# Peripherals.net
KiCad netlist of a schematic drawn in Altium Designer
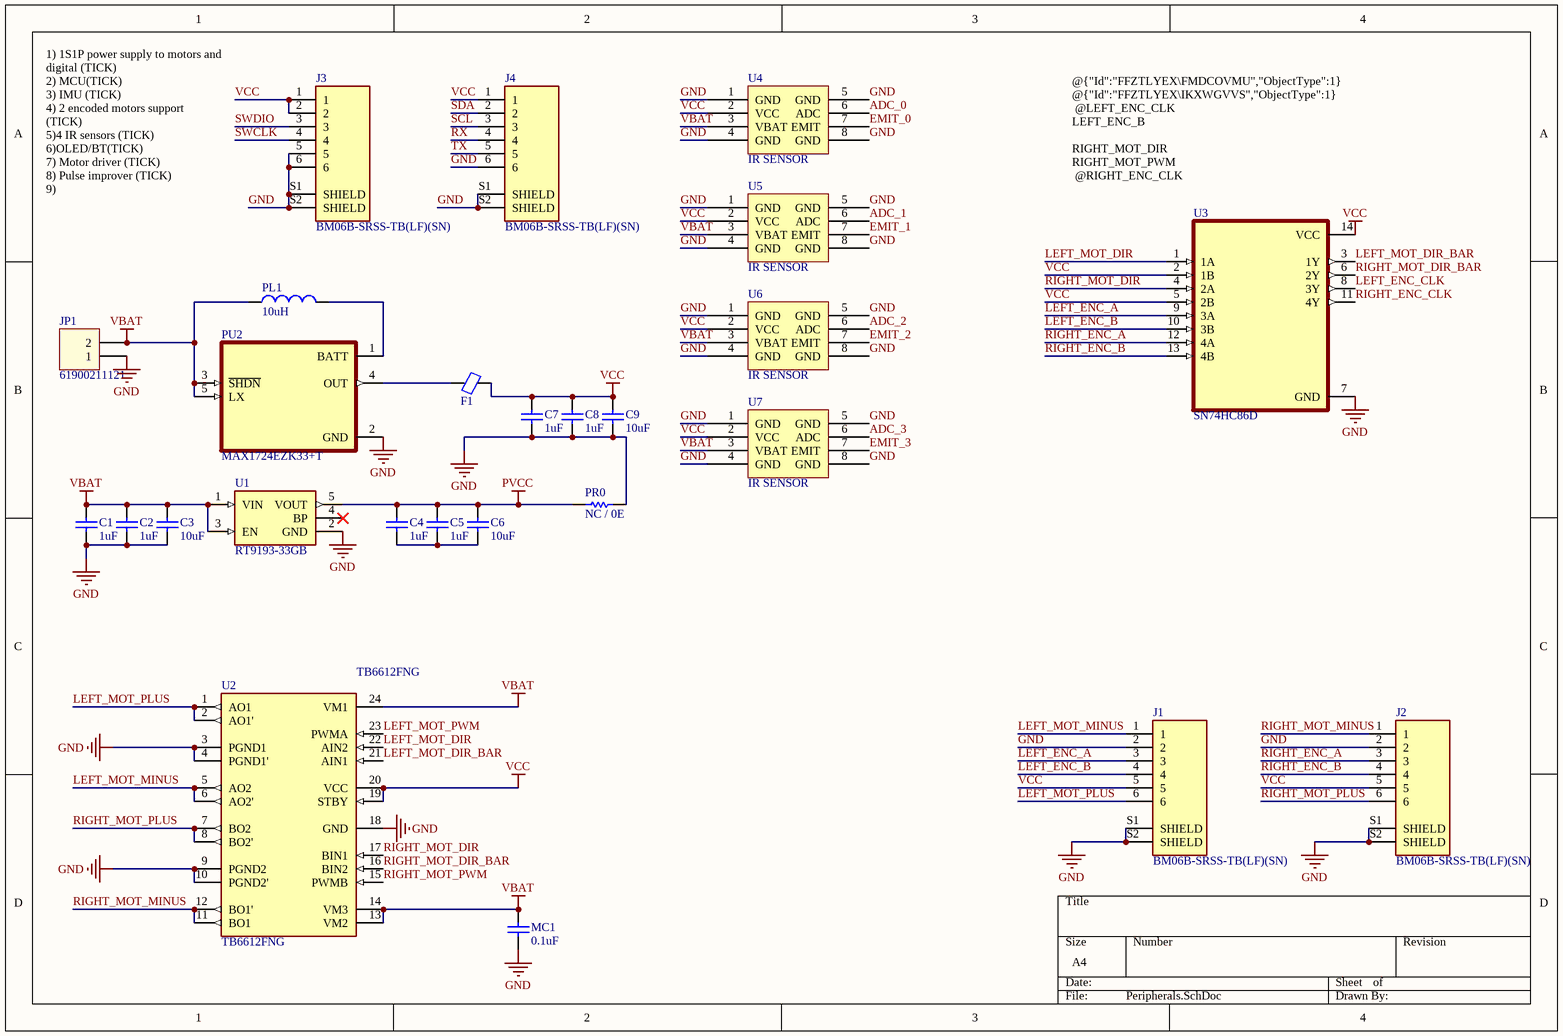
[diagram p0: Peripherals.SchDoc]

(export (version "E")
  (design (tool "Eeschema 10.0.6"))
  (components
    (comp (ref "C1")
      (value "1uF")
      (footprint "CAP0603")
      (description "0603 CAPACITOR SMD")
      (fields (field (name "DESIGNER") "Abbas Basereh"))
      (libsource (lib "Altium") (part "CAP SMD PACKAGE"))
    )
    (comp (ref "C2")
      (value "1uF")
      (footprint "CAP0603")
      (description "0603 CAPACITOR SMD")
      (fields (field (name "DESIGNER") "Abbas Basereh"))
      (libsource (lib "Altium") (part "CAP SMD PACKAGE"))
    )
    (comp (ref "C3")
      (value "10uF")
      (footprint "CAP0603")
      (description "0603 CAPACITOR SMD")
      (fields (field (name "DESIGNER") "Abbas Basereh"))
      (libsource (lib "Altium") (part "CAP SMD PACKAGE"))
    )
    (comp (ref "C4")
      (value "1uF")
      (footprint "CAP0603")
      (description "0603 CAPACITOR SMD")
      (fields (field (name "DESIGNER") "Abbas Basereh"))
      (libsource (lib "Altium") (part "CAP SMD PACKAGE"))
    )
    (comp (ref "C5")
      (value "1uF")
      (footprint "CAP0603")
      (description "0603 CAPACITOR SMD")
      (fields (field (name "DESIGNER") "Abbas Basereh"))
      (libsource (lib "Altium") (part "CAP SMD PACKAGE"))
    )
    (comp (ref "C6")
      (value "10uF")
      (footprint "CAP0603")
      (description "0603 CAPACITOR SMD")
      (fields (field (name "DESIGNER") "Abbas Basereh"))
      (libsource (lib "Altium") (part "CAP SMD PACKAGE"))
    )
    (comp (ref "C7")
      (value "1uF")
      (footprint "CAP0603")
      (description "0603 CAPACITOR SMD")
      (fields (field (name "DESIGNER") "Abbas Basereh"))
      (libsource (lib "Altium") (part "CAP SMD PACKAGE"))
    )
    (comp (ref "C8")
      (value "1uF")
      (footprint "CAP0603")
      (description "0603 CAPACITOR SMD")
      (fields (field (name "DESIGNER") "Abbas Basereh"))
      (libsource (lib "Altium") (part "CAP SMD PACKAGE"))
    )
    (comp (ref "C9")
      (value "10uF")
      (footprint "CAP0603")
      (description "0603 CAPACITOR SMD")
      (fields (field (name "DESIGNER") "Abbas Basereh"))
      (libsource (lib "Altium") (part "CAP SMD PACKAGE"))
    )
    (comp (ref "F1")
      (value "Ferrite Bead SMD")
      (footprint "FB0603")
      (description "0603 FERRITE")
      (fields (field (name "DESIGNER") "Ali Hafizi"))
      (libsource (lib "Altium") (part "Ferrite Bead SMD Package"))
    )
    (comp (ref "J1")
      (value "BM06B-SRSS-TB(LF)(SN)")
      (footprint "JST_BM06B-SRSS-TB(LF)(SN)")
      (libsource (lib "BM06B-SRSS-TB_LF__SN_") (part "BM06B-SRSS-TB(LF)(SN)"))
    )
    (comp (ref "J2")
      (value "BM06B-SRSS-TB(LF)(SN)")
      (footprint "JST_BM06B-SRSS-TB(LF)(SN)")
      (libsource (lib "BM06B-SRSS-TB_LF__SN_") (part "BM06B-SRSS-TB(LF)(SN)"))
    )
    (comp (ref "J3")
      (value "BM06B-SRSS-TB(LF)(SN)")
      (footprint "JST_BM06B-SRSS-TB(LF)(SN)")
      (libsource (lib "BM06B-SRSS-TB_LF__SN_") (part "BM06B-SRSS-TB(LF)(SN)"))
    )
    (comp (ref "J4")
      (value "BM06B-SRSS-TB(LF)(SN)")
      (footprint "JST_BM06B-SRSS-TB(LF)(SN)")
      (libsource (lib "BM06B-SRSS-TB_LF__SN_") (part "BM06B-SRSS-TB(LF)(SN)"))
    )
    (comp (ref "JP1")
      (value "61900211121")
      (footprint "61900211121")
      (description "WR-WTB 2.54mm Male Locking Header, 2p")
      (fields (field (name "PUBLISHER") "Wurth Elektronik"))
      (libsource (lib "Relimate") (part "61900211121"))
    )
    (comp (ref "MC1")
      (value "0.1uF")
      (footprint "Cap1206_(3216X18L)Size A")
      (description "TOTAL CAPACITOR SMD PACK")
      (fields (field (name "DESIGNER") "Abbas Basereh"))
      (libsource (lib "Altium") (part "CAP SMD PACKAGE"))
    )
    (comp (ref "PL1")
      (value "10uH")
      (footprint "IND0805")
      (description "TOTAL INDUCTOR SMD PACK")
      (fields (field (name "DESIGNER") "Abbas Basereh"))
      (libsource (lib "Altium") (part "INDUCTOR SMD PACKAGE"))
    )
    (comp (ref "PR0")
      (value "NC / 0E")
      (footprint "RESC3413X04N")
      (description "RES 0805")
      (fields (field (name "DESIGNER") "Abbas Basereh"))
      (libsource (lib "Altium") (part "RES 0805 0.125W"))
    )
    (comp (ref "PU2")
      (value "MAX1724EZK33+T")
      (footprint "SOT95P275X110-5N")
      (description "Boost Switching Regulator IC Positive Fixed 3.3V 1 Output 400mA _Switch_ SOT-23-5 Thin, TSOT-23-5")
      (fields (field (name "MF") "Maxim Integrated"))
      (libsource (lib "MAX1724EZK33_T") (part "MAX1724EZK33+T"))
    )
    (comp (ref "U1")
      (value "RT9193-33GB")
      (footprint "SOT94P279X129-5N")
      (description "Linear Voltage Regulator IC Positive Fixed 1 Output 300mA TSOT-23-5")
      (fields (field (name "MF") "Richtek USA") (field (name "DIGI-KEY_PART_NUMBER") "1028-1014-2-ND"))
      (libsource (lib "RT9193-33GB") (part "RT9193-33GB"))
    )
    (comp (ref "U2")
      (value "TB6612FNG")
      (footprint "SSOP24")
      (description "- Motor Driver Power MOSFET Parallel 24-SSOP")
      (fields (field (name "MF") "Toshiba"))
      (libsource (lib "TB6612FNG") (part "TB6612FNG"))
    )
    (comp (ref "U3")
      (value "SN74HC86D")
      (footprint "SOIC127P600X175-14N")
      (description "Quadruple 2-Input Exclusive-OR Gates 14-SOIC -40 to 85")
      (fields
        (field (name "MF") "Texas Instruments")
        (field (name "DIGI-KEY_PART_NUMBER") "2156-SN74HC86DRE4-ND")
      )
      (libsource (lib "SN74HC86D") (part "SN74HC86D"))
    )
    (comp (ref "U4")
      (value "IR SENSOR")
      (footprint "BLASTER")
      (libsource (lib "MicroBlaster_lib") (part "Blaster"))
    )
    (comp (ref "U5")
      (value "IR SENSOR")
      (footprint "BLASTER")
      (libsource (lib "MicroBlaster_lib") (part "Blaster"))
    )
    (comp (ref "U6")
      (value "IR SENSOR")
      (footprint "BLASTER")
      (libsource (lib "MicroBlaster_lib") (part "Blaster"))
    )
    (comp (ref "U7")
      (value "IR SENSOR")
      (footprint "BLASTER")
      (libsource (lib "MicroBlaster_lib") (part "Blaster"))
    )
  )
  (nets
    (net (code "1") (name "/ADC_0") (class "Default")
      (node (ref "U4") (pin "6") (pinfunction "ADC_6") (pintype "passive"))
    )
    (net (code "2") (name "/ADC_1") (class "Default")
      (node (ref "U5") (pin "6") (pinfunction "ADC_6") (pintype "passive"))
    )
    (net (code "3") (name "/ADC_2") (class "Default")
      (node (ref "U6") (pin "6") (pinfunction "ADC_6") (pintype "passive"))
    )
    (net (code "4") (name "/ADC_3") (class "Default")
      (node (ref "U7") (pin "6") (pinfunction "ADC_6") (pintype "passive"))
    )
    (net (code "5") (name "/EMIT_0") (class "Default")
      (node (ref "U4") (pin "7") (pinfunction "EMIT_7") (pintype "passive"))
    )
    (net (code "6") (name "/EMIT_1") (class "Default")
      (node (ref "U5") (pin "7") (pinfunction "EMIT_7") (pintype "passive"))
    )
    (net (code "7") (name "/EMIT_2") (class "Default")
      (node (ref "U6") (pin "7") (pinfunction "EMIT_7") (pintype "passive"))
    )
    (net (code "8") (name "/EMIT_3") (class "Default")
      (node (ref "U7") (pin "7") (pinfunction "EMIT_7") (pintype "passive"))
    )
    (net (code "9") (name "/LEFT_ENC_A") (class "Default")
      (node (ref "J1") (pin "3") (pinfunction "3_3") (pintype "passive"))
      (node (ref "U3") (pin "9") (pinfunction "3A_9") (pintype "input"))
    )
    (net (code "10") (name "/LEFT_ENC_B") (class "Default")
      (node (ref "J1") (pin "4") (pinfunction "4_4") (pintype "passive"))
      (node (ref "U3") (pin "10") (pinfunction "3B_10") (pintype "input"))
    )
    (net (code "11") (name "/LEFT_ENC_CLK") (class "Default")
      (node (ref "U3") (pin "8") (pinfunction "3Y_8") (pintype "output"))
    )
    (net (code "12") (name "/LEFT_MOT_DIR") (class "Default")
      (node (ref "U2") (pin "22") (pinfunction "AIN2_22") (pintype "input"))
      (node (ref "U3") (pin "1") (pinfunction "1A_1") (pintype "input"))
    )
    (net (code "13") (name "/LEFT_MOT_DIR_BAR") (class "Default")
      (node (ref "U2") (pin "21") (pinfunction "AIN1_21") (pintype "input"))
      (node (ref "U3") (pin "3") (pinfunction "1Y_3") (pintype "output"))
    )
    (net (code "14") (name "/LEFT_MOT_MINUS") (class "Default")
      (node (ref "J1") (pin "1") (pinfunction "1_1") (pintype "passive"))
      (node (ref "U2") (pin "5") (pinfunction "AO2_5") (pintype "output"))
      (node (ref "U2") (pin "6") (pinfunction "AO2'_6") (pintype "output"))
    )
    (net (code "15") (name "/LEFT_MOT_PLUS") (class "Default")
      (node (ref "J1") (pin "6") (pinfunction "6_6") (pintype "passive"))
      (node (ref "U2") (pin "1") (pinfunction "AO1_1") (pintype "output"))
      (node (ref "U2") (pin "2") (pinfunction "AO1'_2") (pintype "output"))
    )
    (net (code "16") (name "/LEFT_MOT_PWM") (class "Default")
      (node (ref "U2") (pin "23") (pinfunction "PWMA_23") (pintype "input"))
    )
    (net (code "17") (name "/RIGHT_ENC_A") (class "Default")
      (node (ref "J2") (pin "3") (pinfunction "3_3") (pintype "passive"))
      (node (ref "U3") (pin "12") (pinfunction "4A_12") (pintype "input"))
    )
    (net (code "18") (name "/RIGHT_ENC_B") (class "Default")
      (node (ref "J2") (pin "4") (pinfunction "4_4") (pintype "passive"))
      (node (ref "U3") (pin "13") (pinfunction "4B_13") (pintype "input"))
    )
    (net (code "19") (name "/RIGHT_ENC_CLK") (class "Default")
      (node (ref "U3") (pin "11") (pinfunction "4Y_11") (pintype "output"))
    )
    (net (code "20") (name "/RIGHT_MOT_DIR") (class "Default")
      (node (ref "U2") (pin "17") (pinfunction "BIN1_17") (pintype "input"))
      (node (ref "U3") (pin "4") (pinfunction "2A_4") (pintype "input"))
    )
    (net (code "21") (name "/RIGHT_MOT_DIR_BAR") (class "Default")
      (node (ref "U2") (pin "16") (pinfunction "BIN2_16") (pintype "input"))
      (node (ref "U3") (pin "6") (pinfunction "2Y_6") (pintype "output"))
    )
    (net (code "22") (name "/RIGHT_MOT_MINUS") (class "Default")
      (node (ref "J2") (pin "1") (pinfunction "1_1") (pintype "passive"))
      (node (ref "U2") (pin "11") (pinfunction "BO1_11") (pintype "output"))
      (node (ref "U2") (pin "12") (pinfunction "BO1'_12") (pintype "output"))
    )
    (net (code "23") (name "/RIGHT_MOT_PLUS") (class "Default")
      (node (ref "J2") (pin "6") (pinfunction "6_6") (pintype "passive"))
      (node (ref "U2") (pin "7") (pinfunction "BO2_7") (pintype "output"))
      (node (ref "U2") (pin "8") (pinfunction "BO2'_8") (pintype "output"))
    )
    (net (code "24") (name "/RIGHT_MOT_PWM") (class "Default")
      (node (ref "U2") (pin "15") (pinfunction "PWMB_15") (pintype "input"))
    )
    (net (code "25") (name "/RX") (class "Default")
      (node (ref "J4") (pin "4") (pinfunction "4_4") (pintype "passive"))
    )
    (net (code "26") (name "/SCL") (class "Default")
      (node (ref "J4") (pin "3") (pinfunction "3_3") (pintype "passive"))
    )
    (net (code "27") (name "/SDA") (class "Default")
      (node (ref "J4") (pin "2") (pinfunction "2_2") (pintype "passive"))
    )
    (net (code "28") (name "/SWCLK") (class "Default")
      (node (ref "J3") (pin "4") (pinfunction "4_4") (pintype "passive"))
    )
    (net (code "29") (name "/SWDIO") (class "Default")
      (node (ref "J3") (pin "3") (pinfunction "3_3") (pintype "passive"))
    )
    (net (code "30") (name "/TX") (class "Default")
      (node (ref "J4") (pin "5") (pinfunction "5_5") (pintype "passive"))
    )
    (net (code "31") (name "GND") (class "Default")
      (node (ref "C1") (pin "1") (pinfunction "1_1") (pintype "passive"))
      (node (ref "C2") (pin "1") (pinfunction "1_1") (pintype "passive"))
      (node (ref "C3") (pin "1") (pinfunction "1_1") (pintype "passive"))
      (node (ref "C7") (pin "1") (pinfunction "1_1") (pintype "passive"))
      (node (ref "C8") (pin "1") (pinfunction "1_1") (pintype "passive"))
      (node (ref "C9") (pin "1") (pinfunction "1_1") (pintype "passive"))
      (node (ref "J1") (pin "2") (pinfunction "2_2") (pintype "passive"))
      (node (ref "J1") (pin "S1") (pinfunction "SHIELD_S1") (pintype "passive"))
      (node (ref "J1") (pin "S2") (pinfunction "SHIELD_S2") (pintype "passive"))
      (node (ref "J2") (pin "2") (pinfunction "2_2") (pintype "passive"))
      (node (ref "J2") (pin "S1") (pinfunction "SHIELD_S1") (pintype "passive"))
      (node (ref "J2") (pin "S2") (pinfunction "SHIELD_S2") (pintype "passive"))
      (node (ref "J3") (pin "5") (pinfunction "5_5") (pintype "passive"))
      (node (ref "J3") (pin "6") (pinfunction "6_6") (pintype "passive"))
      (node (ref "J3") (pin "S1") (pinfunction "SHIELD_S1") (pintype "passive"))
      (node (ref "J3") (pin "S2") (pinfunction "SHIELD_S2") (pintype "passive"))
      (node (ref "J4") (pin "6") (pinfunction "6_6") (pintype "passive"))
      (node (ref "J4") (pin "S1") (pinfunction "SHIELD_S1") (pintype "passive"))
      (node (ref "J4") (pin "S2") (pinfunction "SHIELD_S2") (pintype "passive"))
      (node (ref "JP1") (pin "1") (pinfunction "1_1") (pintype "passive"))
      (node (ref "MC1") (pin "1") (pinfunction "1_1") (pintype "passive"))
      (node (ref "PR0") (pin "2") (pinfunction "2_2") (pintype "passive"))
      (node (ref "PU2") (pin "2") (pinfunction "GND_2") (pintype "power_in"))
      (node (ref "U1") (pin "2") (pinfunction "GND_2") (pintype "power_in"))
      (node (ref "U2") (pin "10") (pinfunction "PGND2'_10") (pintype "power_in"))
      (node (ref "U2") (pin "18") (pinfunction "GND_18") (pintype "power_in"))
      (node (ref "U2") (pin "3") (pinfunction "PGND1_3") (pintype "power_in"))
      (node (ref "U2") (pin "4") (pinfunction "PGND1'_4") (pintype "power_in"))
      (node (ref "U2") (pin "9") (pinfunction "PGND2_9") (pintype "power_in"))
      (node (ref "U3") (pin "7") (pinfunction "GND_7") (pintype "power_in"))
      (node (ref "U4") (pin "1") (pinfunction "GND_1") (pintype "passive"))
      (node (ref "U4") (pin "4") (pinfunction "GND_4") (pintype "passive"))
      (node (ref "U4") (pin "5") (pinfunction "GND_5") (pintype "passive"))
      (node (ref "U4") (pin "8") (pinfunction "GND_8") (pintype "passive"))
      (node (ref "U5") (pin "1") (pinfunction "GND_1") (pintype "passive"))
      (node (ref "U5") (pin "4") (pinfunction "GND_4") (pintype "passive"))
      (node (ref "U5") (pin "5") (pinfunction "GND_5") (pintype "passive"))
      (node (ref "U5") (pin "8") (pinfunction "GND_8") (pintype "passive"))
      (node (ref "U6") (pin "1") (pinfunction "GND_1") (pintype "passive"))
      (node (ref "U6") (pin "4") (pinfunction "GND_4") (pintype "passive"))
      (node (ref "U6") (pin "5") (pinfunction "GND_5") (pintype "passive"))
      (node (ref "U6") (pin "8") (pinfunction "GND_8") (pintype "passive"))
      (node (ref "U7") (pin "1") (pinfunction "GND_1") (pintype "passive"))
      (node (ref "U7") (pin "4") (pinfunction "GND_4") (pintype "passive"))
      (node (ref "U7") (pin "5") (pinfunction "GND_5") (pintype "passive"))
      (node (ref "U7") (pin "8") (pinfunction "GND_8") (pintype "passive"))
    )
    (net (code "32") (name "Net-(C4-Pad1)") (class "Default")
      (node (ref "C4") (pin "1") (pinfunction "1_1") (pintype "passive"))
      (node (ref "C5") (pin "1") (pinfunction "1_1") (pintype "passive"))
      (node (ref "C6") (pin "1") (pinfunction "1_1") (pintype "passive"))
    )
    (net (code "33") (name "Net-(PU2-BATT)") (class "Default")
      (node (ref "PL1") (pin "2") (pinfunction "2_2") (pintype "passive"))
      (node (ref "PU2") (pin "1") (pinfunction "BATT_1") (pintype "power_in"))
    )
    (net (code "34") (name "Net-(PU2-OUT)") (class "Default")
      (node (ref "F1") (pin "1") (pinfunction "1_1") (pintype "passive"))
      (node (ref "PU2") (pin "4") (pinfunction "OUT_4") (pintype "output"))
    )
    (net (code "35") (name "PVCC") (class "Default")
      (node (ref "C4") (pin "2") (pinfunction "2_2") (pintype "passive"))
      (node (ref "C5") (pin "2") (pinfunction "2_2") (pintype "passive"))
      (node (ref "C6") (pin "2") (pinfunction "2_2") (pintype "passive"))
      (node (ref "PR0") (pin "1") (pinfunction "1_1") (pintype "passive"))
      (node (ref "U1") (pin "5") (pinfunction "VOUT_5") (pintype "output"))
    )
    (net (code "36") (name "VBAT") (class "Default")
      (node (ref "C1") (pin "2") (pinfunction "2_2") (pintype "passive"))
      (node (ref "C2") (pin "2") (pinfunction "2_2") (pintype "passive"))
      (node (ref "C3") (pin "2") (pinfunction "2_2") (pintype "passive"))
      (node (ref "JP1") (pin "2") (pinfunction "2_2") (pintype "passive"))
      (node (ref "MC1") (pin "2") (pinfunction "2_2") (pintype "passive"))
      (node (ref "PL1") (pin "1") (pinfunction "1_1") (pintype "passive"))
      (node (ref "PU2") (pin "3") (pinfunction "~{SHDN}_3") (pintype "input"))
      (node (ref "PU2") (pin "5") (pinfunction "LX_5") (pintype "input"))
      (node (ref "U1") (pin "1") (pinfunction "VIN_1") (pintype "input"))
      (node (ref "U1") (pin "3") (pinfunction "EN_3") (pintype "input"))
      (node (ref "U2") (pin "13") (pinfunction "VM2_13") (pintype "power_in"))
      (node (ref "U2") (pin "14") (pinfunction "VM3_14") (pintype "power_in"))
      (node (ref "U2") (pin "24") (pinfunction "VM1_24") (pintype "power_in"))
      (node (ref "U4") (pin "3") (pinfunction "VBAT_3") (pintype "passive"))
      (node (ref "U5") (pin "3") (pinfunction "VBAT_3") (pintype "passive"))
      (node (ref "U6") (pin "3") (pinfunction "VBAT_3") (pintype "passive"))
      (node (ref "U7") (pin "3") (pinfunction "VBAT_3") (pintype "passive"))
    )
    (net (code "37") (name "VCC") (class "Default")
      (node (ref "C7") (pin "2") (pinfunction "2_2") (pintype "passive"))
      (node (ref "C8") (pin "2") (pinfunction "2_2") (pintype "passive"))
      (node (ref "C9") (pin "2") (pinfunction "2_2") (pintype "passive"))
      (node (ref "F1") (pin "2") (pinfunction "2_2") (pintype "passive"))
      (node (ref "J1") (pin "5") (pinfunction "5_5") (pintype "passive"))
      (node (ref "J2") (pin "5") (pinfunction "5_5") (pintype "passive"))
      (node (ref "J3") (pin "1") (pinfunction "1_1") (pintype "passive"))
      (node (ref "J3") (pin "2") (pinfunction "2_2") (pintype "passive"))
      (node (ref "J4") (pin "1") (pinfunction "1_1") (pintype "passive"))
      (node (ref "U2") (pin "19") (pinfunction "STBY_19") (pintype "input"))
      (node (ref "U2") (pin "20") (pinfunction "VCC_20") (pintype "power_in"))
      (node (ref "U3") (pin "14") (pinfunction "VCC_14") (pintype "power_in"))
      (node (ref "U3") (pin "2") (pinfunction "1B_2") (pintype "input"))
      (node (ref "U3") (pin "5") (pinfunction "2B_5") (pintype "input"))
      (node (ref "U4") (pin "2") (pinfunction "VCC_2") (pintype "passive"))
      (node (ref "U5") (pin "2") (pinfunction "VCC_2") (pintype "passive"))
      (node (ref "U6") (pin "2") (pinfunction "VCC_2") (pintype "passive"))
      (node (ref "U7") (pin "2") (pinfunction "VCC_2") (pintype "passive"))
    )
    (net (code "38") (name "unconnected-(U1-BP-Pad4)") (class "Default")
      (node (ref "U1") (pin "4") (pinfunction "BP_4") (pintype "passive+no_connect"))
    )
  )
)
